# ProDocument___2023-07-26.net
KiCad netlist of a schematic drawn in EasyEDA Pro
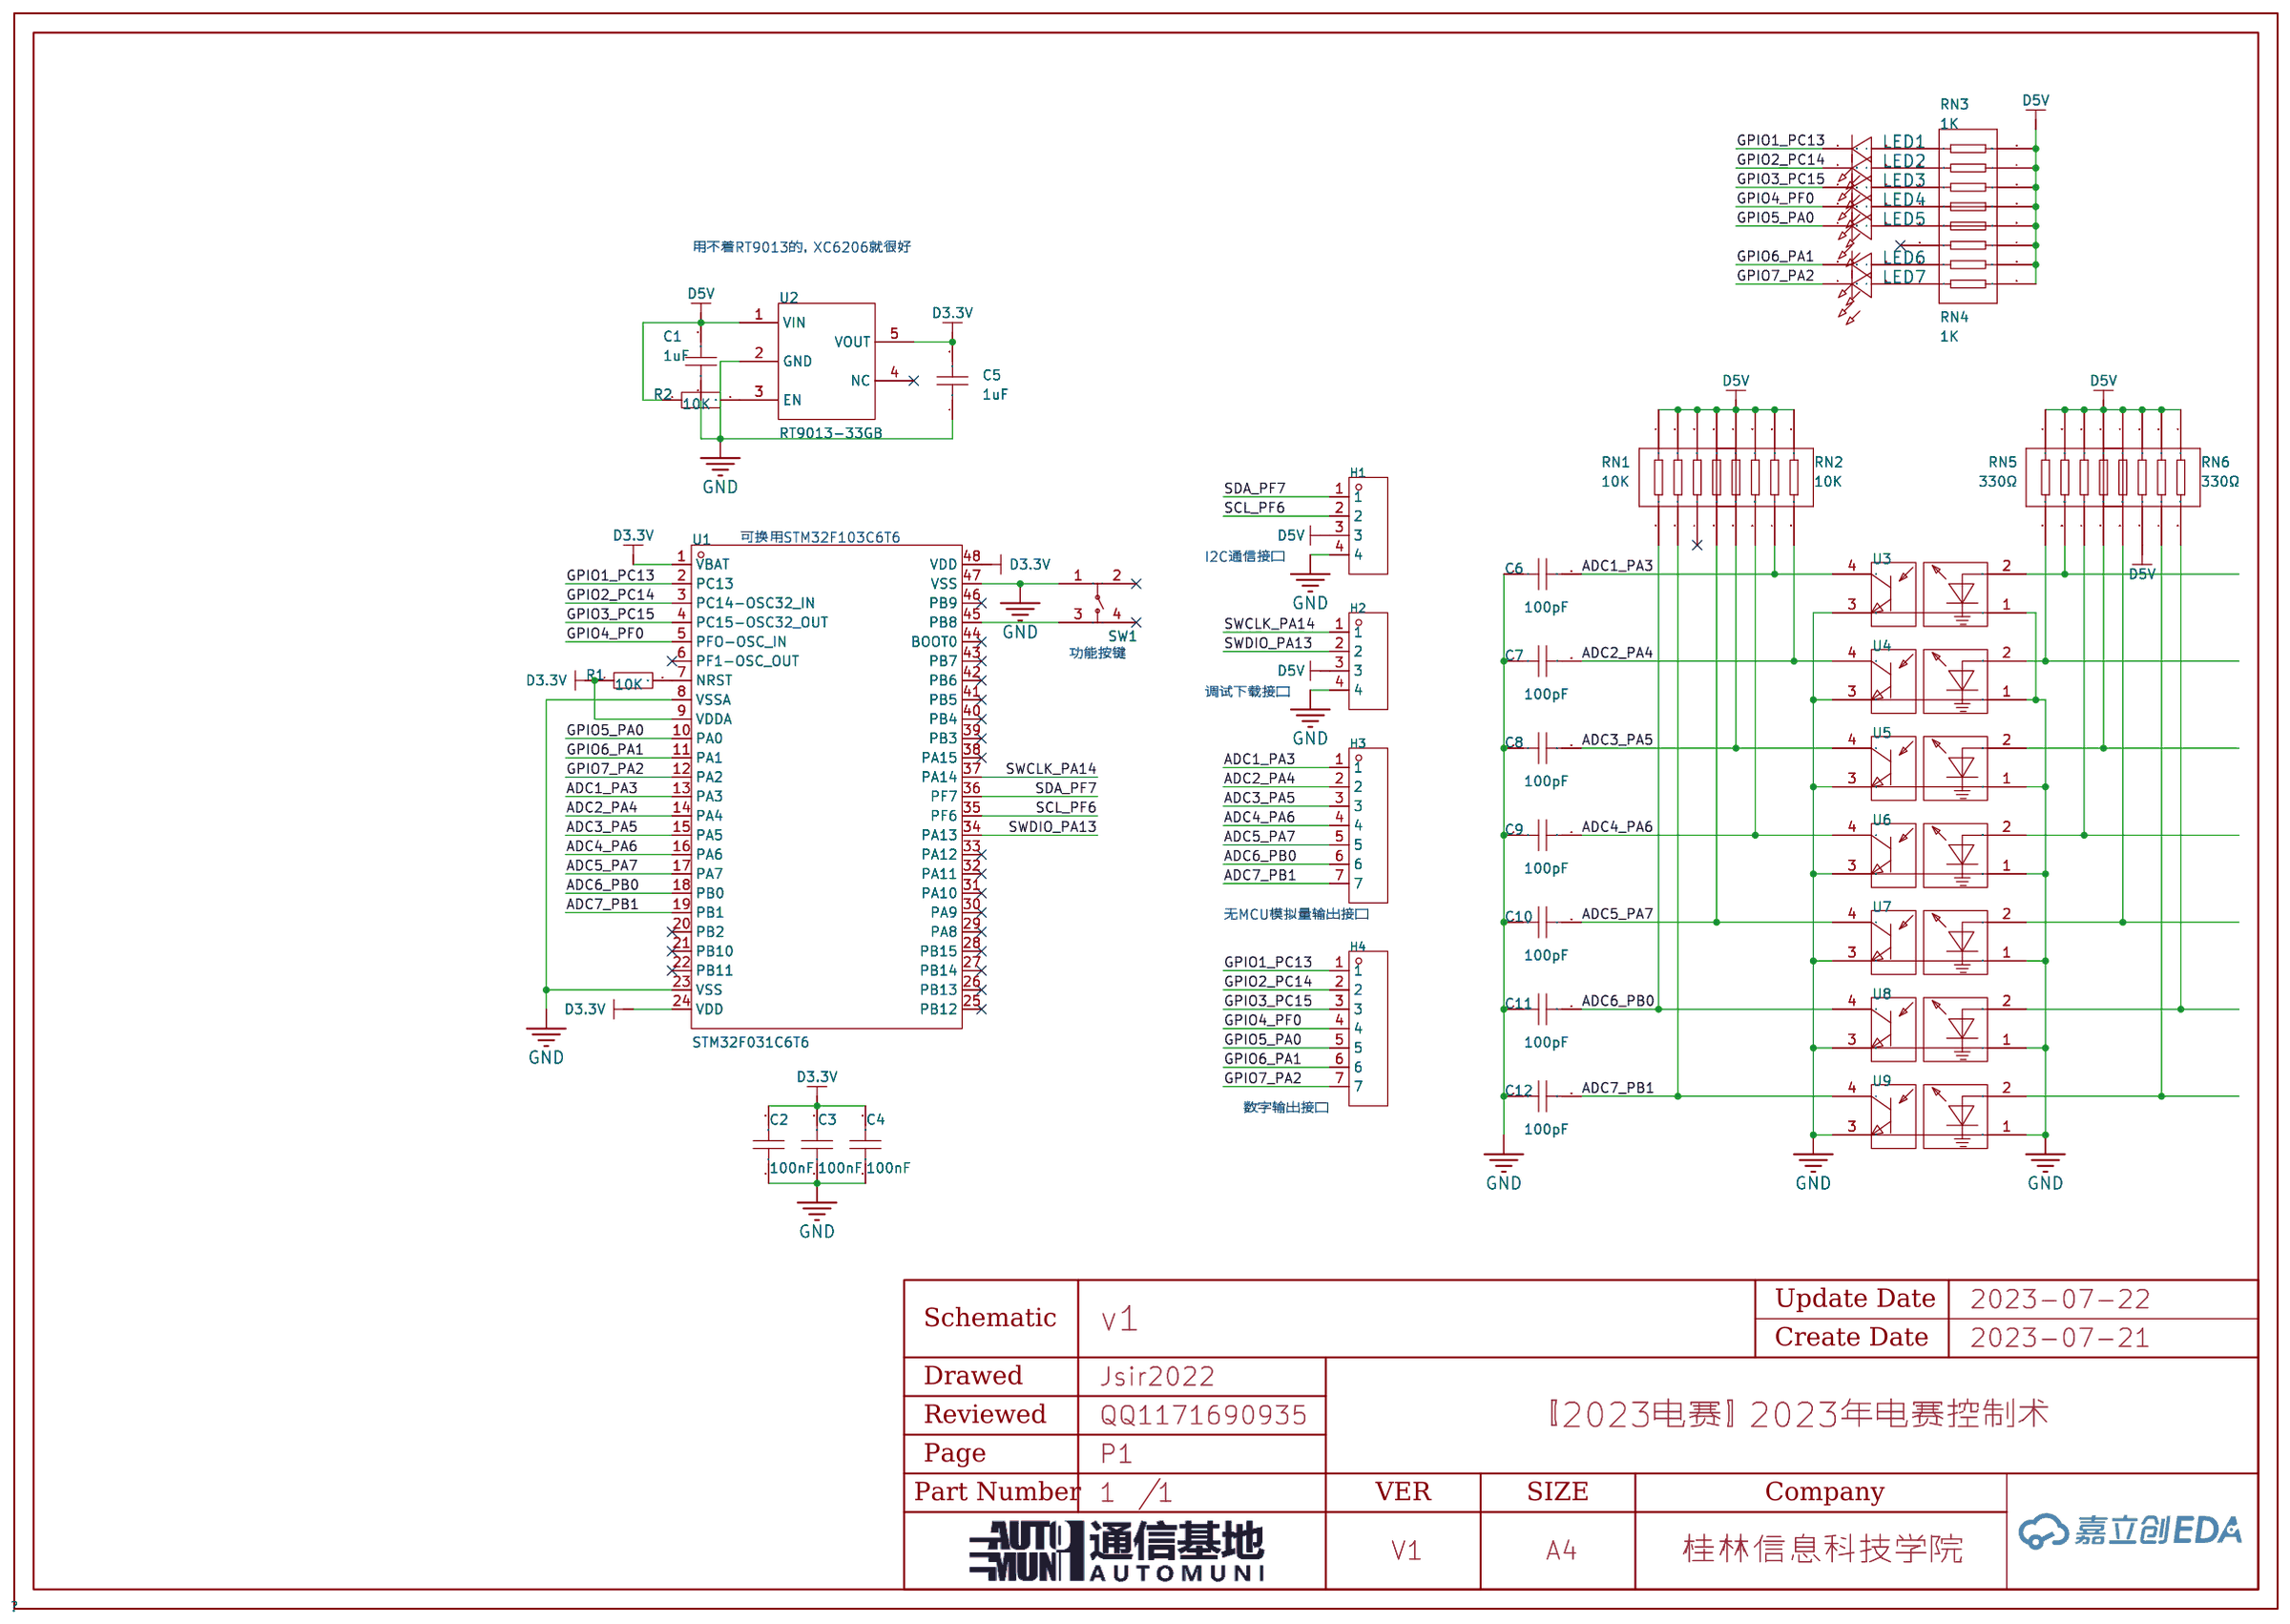
[diagram p0: schematic sheet]

(export (version "E")
  (design (tool "Eeschema 10.0.6"))
  (components
    (comp (ref "C1")
      (value "1uF")
      (footprint "easyedapro:C0603")
      (libsource (lib "easyedapro") (part "CapAcitance"))
    )
    (comp (ref "C2")
      (value "100nF")
      (footprint "easyedapro:C0603")
      (libsource (lib "easyedapro") (part "CapAcitance"))
    )
    (comp (ref "C3")
      (value "100nF")
      (footprint "easyedapro:C0603")
      (libsource (lib "easyedapro") (part "CapAcitance"))
    )
    (comp (ref "C4")
      (value "100nF")
      (footprint "easyedapro:C0603")
      (libsource (lib "easyedapro") (part "CapAcitance"))
    )
    (comp (ref "C5")
      (value "1uF")
      (footprint "easyedapro:C0603")
      (libsource (lib "easyedapro") (part "CapAcitance"))
    )
    (comp (ref "C6")
      (value "100pF")
      (footprint "easyedapro:C0603")
      (libsource (lib "easyedapro") (part "CapAcitance"))
    )
    (comp (ref "C7")
      (value "100pF")
      (footprint "easyedapro:C0603")
      (libsource (lib "easyedapro") (part "CapAcitance"))
    )
    (comp (ref "C8")
      (value "100pF")
      (footprint "easyedapro:C0603")
      (libsource (lib "easyedapro") (part "CapAcitance"))
    )
    (comp (ref "C9")
      (value "100pF")
      (footprint "easyedapro:C0603")
      (libsource (lib "easyedapro") (part "CapAcitance"))
    )
    (comp (ref "C10")
      (value "100pF")
      (footprint "easyedapro:C0603")
      (libsource (lib "easyedapro") (part "CapAcitance"))
    )
    (comp (ref "C11")
      (value "100pF")
      (footprint "easyedapro:C0603")
      (libsource (lib "easyedapro") (part "CapAcitance"))
    )
    (comp (ref "C12")
      (value "100pF")
      (footprint "easyedapro:C0603")
      (libsource (lib "easyedapro") (part "CapAcitance"))
    )
    (comp (ref "H1")
      (value "~")
      (footprint "easyedapro:HDR-TH_4P-P2.54-V-M")
      (libsource (lib "easyedapro") (part "PZ254V-11-04P"))
    )
    (comp (ref "H2")
      (value "~")
      (footprint "easyedapro:HDR-TH_4P-P2.54-V-M")
      (libsource (lib "easyedapro") (part "PZ254V-11-04P"))
    )
    (comp (ref "H3")
      (value "~")
      (footprint "easyedapro:HDR-TH_7P-P2.54-V-M")
      (libsource (lib "easyedapro") (part "PZ254V-11-07P"))
    )
    (comp (ref "H4")
      (value "~")
      (footprint "easyedapro:HDR-TH_7P-P2.54-V-M")
      (libsource (lib "easyedapro") (part "PZ254V-11-07P"))
    )
    (comp (ref "LED1")
      (value "~")
      (footprint "easyedapro:LED_0603")
      (libsource (lib "easyedapro") (part "LED_R"))
    )
    (comp (ref "LED2")
      (value "~")
      (footprint "easyedapro:LED_0603")
      (libsource (lib "easyedapro") (part "LED_R"))
    )
    (comp (ref "LED3")
      (value "~")
      (footprint "easyedapro:LED_0603")
      (libsource (lib "easyedapro") (part "LED_R"))
    )
    (comp (ref "LED4")
      (value "~")
      (footprint "easyedapro:LED_0603")
      (libsource (lib "easyedapro") (part "LED_R"))
    )
    (comp (ref "LED5")
      (value "~")
      (footprint "easyedapro:LED_0603")
      (libsource (lib "easyedapro") (part "LED_R"))
    )
    (comp (ref "LED6")
      (value "~")
      (footprint "easyedapro:LED_0603")
      (libsource (lib "easyedapro") (part "LED_R"))
    )
    (comp (ref "LED7")
      (value "~")
      (footprint "easyedapro:LED_0603")
      (libsource (lib "easyedapro") (part "LED_R"))
    )
    (comp (ref "R1") (value "10K") (footprint "easyedapro:R0603") (libsource (lib "easyedapro") (part "电阻")))
    (comp (ref "R2") (value "10K") (footprint "easyedapro:R0603") (libsource (lib "easyedapro") (part "电阻")))
    (comp (ref "RN1")
      (value "10K")
      (footprint "easyedapro:RES-ARRAY-SMD_0402-8P-L2.0-W1.0-BL")
      (description "阻值:330Ω;精度:±5%;单个元件功率:62.5mW;电阻器数:4;")
      (fields (field (name "Manufacturer Part") "YC124-JR-07330RL") (field (name "Manufacturer") "YAGEO(国巨)"))
      (libsource (lib "easyedapro") (part "YC124-JR-07330RL"))
    )
    (comp (ref "RN2")
      (value "10K")
      (footprint "easyedapro:RES-ARRAY-SMD_0402-8P-L2.0-W1.0-BL")
      (description "阻值:330Ω;精度:±5%;单个元件功率:62.5mW;电阻器数:4;")
      (fields (field (name "Manufacturer Part") "YC124-JR-07330RL") (field (name "Manufacturer") "YAGEO(国巨)"))
      (libsource (lib "easyedapro") (part "YC124-JR-07330RL"))
    )
    (comp (ref "RN3")
      (value "1K")
      (footprint "easyedapro:RES-ARRAY-SMD_0402-8P-L2.0-W1.0-BL")
      (description "阻值:330Ω;精度:±5%;单个元件功率:62.5mW;电阻器数:4;")
      (fields (field (name "Manufacturer Part") "YC124-JR-07330RL") (field (name "Manufacturer") "YAGEO(国巨)"))
      (libsource (lib "easyedapro") (part "YC124-JR-07330RL"))
    )
    (comp (ref "RN4")
      (value "1K")
      (footprint "easyedapro:RES-ARRAY-SMD_0402-8P-L2.0-W1.0-BL")
      (description "阻值:330Ω;精度:±5%;单个元件功率:62.5mW;电阻器数:4;")
      (fields (field (name "Manufacturer Part") "YC124-JR-07330RL") (field (name "Manufacturer") "YAGEO(国巨)"))
      (libsource (lib "easyedapro") (part "YC124-JR-07330RL"))
    )
    (comp (ref "RN5")
      (value "330Ω")
      (footprint "easyedapro:RES-ARRAY-SMD_0402-8P-L2.0-W1.0-BL")
      (description "阻值:330Ω;精度:±5%;单个元件功率:62.5mW;电阻器数:4;")
      (fields (field (name "Manufacturer Part") "YC124-JR-07330RL") (field (name "Manufacturer") "YAGEO(国巨)"))
      (libsource (lib "easyedapro") (part "YC124-JR-07330RL"))
    )
    (comp (ref "RN6")
      (value "330Ω")
      (footprint "easyedapro:RES-ARRAY-SMD_0402-8P-L2.0-W1.0-BL")
      (description "阻值:330Ω;精度:±5%;单个元件功率:62.5mW;电阻器数:4;")
      (fields (field (name "Manufacturer Part") "YC124-JR-07330RL") (field (name "Manufacturer") "YAGEO(国巨)"))
      (libsource (lib "easyedapro") (part "YC124-JR-07330RL"))
    )
    (comp (ref "SW1")
      (value "TS-1089S-AR02516")
      (footprint "easyedapro:SW-SMD_4P-L4.2-W3.3-P2.15-LS5.1")
      (fields (field (name "Manufacturer") "XUNPU(讯普)"))
      (libsource (lib "easyedapro") (part "TS-1089S-AR02516"))
    )
    (comp (ref "U1")
      (value "STM32F031C6T6")
      (footprint "easyedapro:LQFP-48_L7.0-W7.0-P0.50-LS9.0-BL")
      (fields (field (name "Manufacturer") "ST(意法半导体)"))
      (libsource (lib "easyedapro") (part "STM32F031C6T6"))
    )
    (comp (ref "U2")
      (value "RT9013-33GB")
      (footprint "easyedapro:SOT-23-5_L3.0-W1.7-P0.95-LS2.8-BL")
      (description "输出类型:固定;输出极性:正;最大输入电压:5.5V;输出电压:3.3V;输出电流:500mA;电源纹波抑制比(PSRR):50dB@(10kHz);")
      (fields (field (name "Manufacturer") "RICHTEK(立锜)"))
      (libsource (lib "easyedapro") (part "RT9013-33GB"))
    )
    (comp (ref "U3")
      (value "ITR9909")
      (footprint "easyedapro:OPTO-TH_ITR9909")
      (fields (field (name "Manufacturer") "EVERLIGHT(台湾亿光)"))
      (libsource (lib "easyedapro") (part "ITR9909"))
    )
    (comp (ref "U4")
      (value "ITR9909")
      (footprint "easyedapro:OPTO-TH_ITR9909")
      (fields (field (name "Manufacturer") "EVERLIGHT(台湾亿光)"))
      (libsource (lib "easyedapro") (part "ITR9909"))
    )
    (comp (ref "U5")
      (value "ITR9909")
      (footprint "easyedapro:OPTO-TH_ITR9909")
      (fields (field (name "Manufacturer") "EVERLIGHT(台湾亿光)"))
      (libsource (lib "easyedapro") (part "ITR9909"))
    )
    (comp (ref "U6")
      (value "ITR9909")
      (footprint "easyedapro:OPTO-TH_ITR9909")
      (fields (field (name "Manufacturer") "EVERLIGHT(台湾亿光)"))
      (libsource (lib "easyedapro") (part "ITR9909"))
    )
    (comp (ref "U7")
      (value "ITR9909")
      (footprint "easyedapro:OPTO-TH_ITR9909")
      (fields (field (name "Manufacturer") "EVERLIGHT(台湾亿光)"))
      (libsource (lib "easyedapro") (part "ITR9909"))
    )
    (comp (ref "U8")
      (value "ITR9909")
      (footprint "easyedapro:OPTO-TH_ITR9909")
      (fields (field (name "Manufacturer") "EVERLIGHT(台湾亿光)"))
      (libsource (lib "easyedapro") (part "ITR9909"))
    )
    (comp (ref "U9")
      (value "ITR9909")
      (footprint "easyedapro:OPTO-TH_ITR9909")
      (fields (field (name "Manufacturer") "EVERLIGHT(台湾亿光)"))
      (libsource (lib "easyedapro") (part "ITR9909"))
    )
  )
  (nets
    (net (code "1") (name "/ADC1_PA3") (class "Default")
      (node (ref "C6") (pin "2") (pinfunction "2_2") (pintype "input"))
      (node (ref "H3") (pin "1") (pinfunction "1_1") (pintype "input"))
      (node (ref "RN2") (pin "7") (pinfunction "7_7") (pintype "input"))
      (node (ref "U1") (pin "13") (pinfunction "PA3_13") (pintype "input"))
      (node (ref "U3") (pin "4") (pinfunction "4_4") (pintype "input"))
    )
    (net (code "2") (name "/ADC2_PA4") (class "Default")
      (node (ref "C7") (pin "2") (pinfunction "2_2") (pintype "input"))
      (node (ref "H3") (pin "2") (pinfunction "2_2") (pintype "input"))
      (node (ref "RN2") (pin "8") (pinfunction "8_8") (pintype "input"))
      (node (ref "U1") (pin "14") (pinfunction "PA4_14") (pintype "input"))
      (node (ref "U4") (pin "4") (pinfunction "4_4") (pintype "input"))
    )
    (net (code "3") (name "/ADC3_PA5") (class "Default")
      (node (ref "C8") (pin "2") (pinfunction "2_2") (pintype "input"))
      (node (ref "H3") (pin "3") (pinfunction "3_3") (pintype "input"))
      (node (ref "RN2") (pin "5") (pinfunction "5_5") (pintype "input"))
      (node (ref "U1") (pin "15") (pinfunction "PA5_15") (pintype "input"))
      (node (ref "U5") (pin "4") (pinfunction "4_4") (pintype "input"))
    )
    (net (code "4") (name "/ADC4_PA6") (class "Default")
      (node (ref "C9") (pin "2") (pinfunction "2_2") (pintype "input"))
      (node (ref "H3") (pin "4") (pinfunction "4_4") (pintype "input"))
      (node (ref "RN2") (pin "6") (pinfunction "6_6") (pintype "input"))
      (node (ref "U1") (pin "16") (pinfunction "PA6_16") (pintype "input"))
      (node (ref "U6") (pin "4") (pinfunction "4_4") (pintype "input"))
    )
    (net (code "5") (name "/ADC5_PA7") (class "Default")
      (node (ref "C10") (pin "2") (pinfunction "2_2") (pintype "input"))
      (node (ref "H3") (pin "5") (pinfunction "5_5") (pintype "input"))
      (node (ref "RN1") (pin "8") (pinfunction "8_8") (pintype "input"))
      (node (ref "U1") (pin "17") (pinfunction "PA7_17") (pintype "input"))
      (node (ref "U7") (pin "4") (pinfunction "4_4") (pintype "input"))
    )
    (net (code "6") (name "/ADC6_PB0") (class "Default")
      (node (ref "C11") (pin "2") (pinfunction "2_2") (pintype "input"))
      (node (ref "H3") (pin "6") (pinfunction "6_6") (pintype "input"))
      (node (ref "RN1") (pin "5") (pinfunction "5_5") (pintype "input"))
      (node (ref "U1") (pin "18") (pinfunction "PB0_18") (pintype "input"))
      (node (ref "U8") (pin "4") (pinfunction "4_4") (pintype "input"))
    )
    (net (code "7") (name "/ADC7_PB1") (class "Default")
      (node (ref "C12") (pin "2") (pinfunction "2_2") (pintype "input"))
      (node (ref "H3") (pin "7") (pinfunction "7_7") (pintype "input"))
      (node (ref "RN1") (pin "6") (pinfunction "6_6") (pintype "input"))
      (node (ref "U1") (pin "19") (pinfunction "PB1_19") (pintype "input"))
      (node (ref "U9") (pin "4") (pinfunction "4_4") (pintype "input"))
    )
    (net (code "8") (name "/GPIO1_PC13") (class "Default")
      (node (ref "H4") (pin "1") (pinfunction "1_1") (pintype "input"))
      (node (ref "LED1") (pin "1") (pinfunction "C_1") (pintype "input"))
      (node (ref "U1") (pin "2") (pinfunction "PC13_2") (pintype "input"))
    )
    (net (code "9") (name "/GPIO2_PC14") (class "Default")
      (node (ref "H4") (pin "2") (pinfunction "2_2") (pintype "input"))
      (node (ref "LED2") (pin "1") (pinfunction "C_1") (pintype "input"))
      (node (ref "U1") (pin "3") (pinfunction "PC14-OSC32_IN_3") (pintype "input"))
    )
    (net (code "10") (name "/GPIO3_PC15") (class "Default")
      (node (ref "H4") (pin "3") (pinfunction "3_3") (pintype "input"))
      (node (ref "LED3") (pin "1") (pinfunction "C_1") (pintype "input"))
      (node (ref "U1") (pin "4") (pinfunction "PC15-OSC32_OUT_4") (pintype "input"))
    )
    (net (code "11") (name "/GPIO4_PF0") (class "Default")
      (node (ref "H4") (pin "4") (pinfunction "4_4") (pintype "input"))
      (node (ref "LED4") (pin "1") (pinfunction "C_1") (pintype "input"))
      (node (ref "U1") (pin "5") (pinfunction "PFO-OSC_IN_5") (pintype "input"))
    )
    (net (code "12") (name "/GPIO5_PA0") (class "Default")
      (node (ref "H4") (pin "5") (pinfunction "5_5") (pintype "input"))
      (node (ref "LED5") (pin "1") (pinfunction "C_1") (pintype "input"))
      (node (ref "U1") (pin "10") (pinfunction "PA0_10") (pintype "input"))
    )
    (net (code "13") (name "/GPIO6_PA1") (class "Default")
      (node (ref "H4") (pin "6") (pinfunction "6_6") (pintype "input"))
      (node (ref "LED6") (pin "1") (pinfunction "C_1") (pintype "input"))
      (node (ref "U1") (pin "11") (pinfunction "PA1_11") (pintype "input"))
    )
    (net (code "14") (name "/GPIO7_PA2") (class "Default")
      (node (ref "H4") (pin "7") (pinfunction "7_7") (pintype "input"))
      (node (ref "LED7") (pin "1") (pinfunction "C_1") (pintype "input"))
      (node (ref "U1") (pin "12") (pinfunction "PA2_12") (pintype "input"))
    )
    (net (code "15") (name "/SCL_PF6") (class "Default")
      (node (ref "H1") (pin "2") (pinfunction "2_2") (pintype "input"))
      (node (ref "U1") (pin "35") (pinfunction "PF6_35") (pintype "input"))
    )
    (net (code "16") (name "/SDA_PF7") (class "Default")
      (node (ref "H1") (pin "1") (pinfunction "1_1") (pintype "input"))
      (node (ref "U1") (pin "36") (pinfunction "PF7_36") (pintype "input"))
    )
    (net (code "17") (name "/SWCLK_PA14") (class "Default")
      (node (ref "H2") (pin "1") (pinfunction "1_1") (pintype "input"))
      (node (ref "U1") (pin "37") (pinfunction "PA14_37") (pintype "input"))
    )
    (net (code "18") (name "/SWDIO_PA13") (class "Default")
      (node (ref "H2") (pin "2") (pinfunction "2_2") (pintype "input"))
      (node (ref "U1") (pin "34") (pinfunction "PA13_34") (pintype "input"))
    )
    (net (code "19") (name "D3.3V") (class "Default")
      (node (ref "C2") (pin "2") (pinfunction "2_2") (pintype "input"))
      (node (ref "C3") (pin "2") (pinfunction "2_2") (pintype "input"))
      (node (ref "C4") (pin "2") (pinfunction "2_2") (pintype "input"))
      (node (ref "C5") (pin "2") (pinfunction "2_2") (pintype "input"))
      (node (ref "R1") (pin "1") (pinfunction "1_1") (pintype "input"))
      (node (ref "U1") (pin "1") (pinfunction "VBAT_1") (pintype "input"))
      (node (ref "U1") (pin "24") (pinfunction "VDD_24") (pintype "input"))
      (node (ref "U1") (pin "48") (pinfunction "VDD_48") (pintype "input"))
      (node (ref "U1") (pin "9") (pinfunction "VDDA_9") (pintype "input"))
      (node (ref "U2") (pin "5") (pinfunction "VOUT_5") (pintype "input"))
    )
    (net (code "20") (name "D5V") (class "Default")
      (node (ref "C1") (pin "2") (pinfunction "2_2") (pintype "input"))
      (node (ref "H1") (pin "3") (pinfunction "3_3") (pintype "input"))
      (node (ref "H2") (pin "3") (pinfunction "3_3") (pintype "input"))
      (node (ref "R2") (pin "1") (pinfunction "1_1") (pintype "input"))
      (node (ref "RN1") (pin "1") (pinfunction "1_1") (pintype "input"))
      (node (ref "RN1") (pin "2") (pinfunction "2_2") (pintype "input"))
      (node (ref "RN1") (pin "3") (pinfunction "3_3") (pintype "input"))
      (node (ref "RN1") (pin "4") (pinfunction "4_4") (pintype "input"))
      (node (ref "RN2") (pin "1") (pinfunction "1_1") (pintype "input"))
      (node (ref "RN2") (pin "2") (pinfunction "2_2") (pintype "input"))
      (node (ref "RN2") (pin "3") (pinfunction "3_3") (pintype "input"))
      (node (ref "RN2") (pin "4") (pinfunction "4_4") (pintype "input"))
      (node (ref "RN3") (pin "5") (pinfunction "5_5") (pintype "input"))
      (node (ref "RN3") (pin "6") (pinfunction "6_6") (pintype "input"))
      (node (ref "RN3") (pin "7") (pinfunction "7_7") (pintype "input"))
      (node (ref "RN3") (pin "8") (pinfunction "8_8") (pintype "input"))
      (node (ref "RN4") (pin "5") (pinfunction "5_5") (pintype "input"))
      (node (ref "RN4") (pin "6") (pinfunction "6_6") (pintype "input"))
      (node (ref "RN4") (pin "7") (pinfunction "7_7") (pintype "input"))
      (node (ref "RN4") (pin "8") (pinfunction "8_8") (pintype "input"))
      (node (ref "RN5") (pin "1") (pinfunction "1_1") (pintype "input"))
      (node (ref "RN5") (pin "2") (pinfunction "2_2") (pintype "input"))
      (node (ref "RN5") (pin "3") (pinfunction "3_3") (pintype "input"))
      (node (ref "RN5") (pin "4") (pinfunction "4_4") (pintype "input"))
      (node (ref "RN6") (pin "1") (pinfunction "1_1") (pintype "input"))
      (node (ref "RN6") (pin "2") (pinfunction "2_2") (pintype "input"))
      (node (ref "RN6") (pin "3") (pinfunction "3_3") (pintype "input"))
      (node (ref "RN6") (pin "4") (pinfunction "4_4") (pintype "input"))
      (node (ref "RN6") (pin "6") (pinfunction "6_6") (pintype "input"))
      (node (ref "U2") (pin "1") (pinfunction "VIN_1") (pintype "input"))
    )
    (net (code "21") (name "GND") (class "Default")
      (node (ref "C1") (pin "1") (pinfunction "1_1") (pintype "input"))
      (node (ref "C10") (pin "1") (pinfunction "1_1") (pintype "input"))
      (node (ref "C11") (pin "1") (pinfunction "1_1") (pintype "input"))
      (node (ref "C12") (pin "1") (pinfunction "1_1") (pintype "input"))
      (node (ref "C2") (pin "1") (pinfunction "1_1") (pintype "input"))
      (node (ref "C3") (pin "1") (pinfunction "1_1") (pintype "input"))
      (node (ref "C4") (pin "1") (pinfunction "1_1") (pintype "input"))
      (node (ref "C5") (pin "1") (pinfunction "1_1") (pintype "input"))
      (node (ref "C6") (pin "1") (pinfunction "1_1") (pintype "input"))
      (node (ref "C7") (pin "1") (pinfunction "1_1") (pintype "input"))
      (node (ref "C8") (pin "1") (pinfunction "1_1") (pintype "input"))
      (node (ref "C9") (pin "1") (pinfunction "1_1") (pintype "input"))
      (node (ref "H1") (pin "4") (pinfunction "4_4") (pintype "input"))
      (node (ref "H2") (pin "4") (pinfunction "4_4") (pintype "input"))
      (node (ref "SW1") (pin "1") (pinfunction "1_1") (pintype "input"))
      (node (ref "U1") (pin "23") (pinfunction "VSS_23") (pintype "input"))
      (node (ref "U1") (pin "47") (pinfunction "VSS_47") (pintype "input"))
      (node (ref "U1") (pin "8") (pinfunction "VSSA_8") (pintype "input"))
      (node (ref "U2") (pin "2") (pinfunction "GND_2") (pintype "input"))
      (node (ref "U3") (pin "1") (pinfunction "1_1") (pintype "input"))
      (node (ref "U3") (pin "3") (pinfunction "3_3") (pintype "input"))
      (node (ref "U4") (pin "1") (pinfunction "1_1") (pintype "input"))
      (node (ref "U4") (pin "3") (pinfunction "3_3") (pintype "input"))
      (node (ref "U5") (pin "1") (pinfunction "1_1") (pintype "input"))
      (node (ref "U5") (pin "3") (pinfunction "3_3") (pintype "input"))
      (node (ref "U6") (pin "1") (pinfunction "1_1") (pintype "input"))
      (node (ref "U6") (pin "3") (pinfunction "3_3") (pintype "input"))
      (node (ref "U7") (pin "1") (pinfunction "1_1") (pintype "input"))
      (node (ref "U7") (pin "3") (pinfunction "3_3") (pintype "input"))
      (node (ref "U8") (pin "1") (pinfunction "1_1") (pintype "input"))
      (node (ref "U8") (pin "3") (pinfunction "3_3") (pintype "input"))
      (node (ref "U9") (pin "1") (pinfunction "1_1") (pintype "input"))
      (node (ref "U9") (pin "3") (pinfunction "3_3") (pintype "input"))
    )
    (net (code "22") (name "Net-(LED1-A)") (class "Default")
      (node (ref "LED1") (pin "2") (pinfunction "A_2") (pintype "input"))
      (node (ref "RN3") (pin "1") (pinfunction "1_1") (pintype "input"))
    )
    (net (code "23") (name "Net-(LED2-A)") (class "Default")
      (node (ref "LED2") (pin "2") (pinfunction "A_2") (pintype "input"))
      (node (ref "RN3") (pin "2") (pinfunction "2_2") (pintype "input"))
    )
    (net (code "24") (name "Net-(LED3-A)") (class "Default")
      (node (ref "LED3") (pin "2") (pinfunction "A_2") (pintype "input"))
      (node (ref "RN3") (pin "3") (pinfunction "3_3") (pintype "input"))
    )
    (net (code "25") (name "Net-(LED4-A)") (class "Default")
      (node (ref "LED4") (pin "2") (pinfunction "A_2") (pintype "input"))
      (node (ref "RN3") (pin "4") (pinfunction "4_4") (pintype "input"))
    )
    (net (code "26") (name "Net-(LED5-A)") (class "Default")
      (node (ref "LED5") (pin "2") (pinfunction "A_2") (pintype "input"))
      (node (ref "RN4") (pin "1") (pinfunction "1_1") (pintype "input"))
    )
    (net (code "27") (name "Net-(LED6-A)") (class "Default")
      (node (ref "LED6") (pin "2") (pinfunction "A_2") (pintype "input"))
      (node (ref "RN4") (pin "3") (pinfunction "3_3") (pintype "input"))
    )
    (net (code "28") (name "Net-(LED7-A)") (class "Default")
      (node (ref "LED7") (pin "2") (pinfunction "A_2") (pintype "input"))
      (node (ref "RN4") (pin "4") (pinfunction "4_4") (pintype "input"))
    )
    (net (code "29") (name "Net-(RN5-Pad5)") (class "Default")
      (node (ref "RN5") (pin "5") (pinfunction "5_5") (pintype "input"))
      (node (ref "U4") (pin "2") (pinfunction "2_2") (pintype "input"))
    )
    (net (code "30") (name "Net-(RN5-Pad6)") (class "Default")
      (node (ref "RN5") (pin "6") (pinfunction "6_6") (pintype "input"))
      (node (ref "U3") (pin "2") (pinfunction "2_2") (pintype "input"))
    )
    (net (code "31") (name "Net-(RN5-Pad7)") (class "Default")
      (node (ref "RN5") (pin "7") (pinfunction "7_7") (pintype "input"))
      (node (ref "U6") (pin "2") (pinfunction "2_2") (pintype "input"))
    )
    (net (code "32") (name "Net-(RN5-Pad8)") (class "Default")
      (node (ref "RN5") (pin "8") (pinfunction "8_8") (pintype "input"))
      (node (ref "U5") (pin "2") (pinfunction "2_2") (pintype "input"))
    )
    (net (code "33") (name "Net-(RN6-Pad5)") (class "Default")
      (node (ref "RN6") (pin "5") (pinfunction "5_5") (pintype "input"))
      (node (ref "U7") (pin "2") (pinfunction "2_2") (pintype "input"))
    )
    (net (code "34") (name "Net-(RN6-Pad7)") (class "Default")
      (node (ref "RN6") (pin "7") (pinfunction "7_7") (pintype "input"))
      (node (ref "U9") (pin "2") (pinfunction "2_2") (pintype "input"))
    )
    (net (code "35") (name "Net-(RN6-Pad8)") (class "Default")
      (node (ref "RN6") (pin "8") (pinfunction "8_8") (pintype "input"))
      (node (ref "U8") (pin "2") (pinfunction "2_2") (pintype "input"))
    )
    (net (code "36") (name "Net-(U1-NRST)") (class "Default")
      (node (ref "R1") (pin "2") (pinfunction "2_2") (pintype "input"))
      (node (ref "U1") (pin "7") (pinfunction "NRST_7") (pintype "input"))
    )
    (net (code "37") (name "Net-(U1-PB8)") (class "Default")
      (node (ref "SW1") (pin "3") (pinfunction "3_3") (pintype "input"))
      (node (ref "U1") (pin "45") (pinfunction "PB8_45") (pintype "input"))
    )
    (net (code "38") (name "Net-(U2-EN)") (class "Default")
      (node (ref "R2") (pin "2") (pinfunction "2_2") (pintype "input"))
      (node (ref "U2") (pin "3") (pinfunction "EN_3") (pintype "input"))
    )
    (net (code "39") (name "unconnected-(RN1-Pad7)") (class "Default")
      (node (ref "RN1") (pin "7") (pinfunction "7_7") (pintype "input+no_connect"))
    )
    (net (code "40") (name "unconnected-(RN4-Pad2)") (class "Default")
      (node (ref "RN4") (pin "2") (pinfunction "2_2") (pintype "input+no_connect"))
    )
    (net (code "41") (name "unconnected-(SW1-Pad2)") (class "Default")
      (node (ref "SW1") (pin "2") (pinfunction "2_2") (pintype "input+no_connect"))
    )
    (net (code "42") (name "unconnected-(SW1-Pad4)") (class "Default")
      (node (ref "SW1") (pin "4") (pinfunction "4_4") (pintype "input+no_connect"))
    )
    (net (code "43") (name "unconnected-(U1-BOOT0-Pad44)") (class "Default")
      (node (ref "U1") (pin "44") (pinfunction "BOOT0_44") (pintype "input+no_connect"))
    )
    (net (code "44") (name "unconnected-(U1-PA8-Pad29)") (class "Default")
      (node (ref "U1") (pin "29") (pinfunction "PA8_29") (pintype "input+no_connect"))
    )
    (net (code "45") (name "unconnected-(U1-PA9-Pad30)") (class "Default")
      (node (ref "U1") (pin "30") (pinfunction "PA9_30") (pintype "input+no_connect"))
    )
    (net (code "46") (name "unconnected-(U1-PA10-Pad31)") (class "Default")
      (node (ref "U1") (pin "31") (pinfunction "PA10_31") (pintype "input+no_connect"))
    )
    (net (code "47") (name "unconnected-(U1-PA11-Pad32)") (class "Default")
      (node (ref "U1") (pin "32") (pinfunction "PA11_32") (pintype "input+no_connect"))
    )
    (net (code "48") (name "unconnected-(U1-PA12-Pad33)") (class "Default")
      (node (ref "U1") (pin "33") (pinfunction "PA12_33") (pintype "input+no_connect"))
    )
    (net (code "49") (name "unconnected-(U1-PA15-Pad38)") (class "Default")
      (node (ref "U1") (pin "38") (pinfunction "PA15_38") (pintype "input+no_connect"))
    )
    (net (code "50") (name "unconnected-(U1-PB2-Pad20)") (class "Default")
      (node (ref "U1") (pin "20") (pinfunction "PB2_20") (pintype "input+no_connect"))
    )
    (net (code "51") (name "unconnected-(U1-PB3-Pad39)") (class "Default")
      (node (ref "U1") (pin "39") (pinfunction "PB3_39") (pintype "input+no_connect"))
    )
    (net (code "52") (name "unconnected-(U1-PB4-Pad40)") (class "Default")
      (node (ref "U1") (pin "40") (pinfunction "PB4_40") (pintype "input+no_connect"))
    )
    (net (code "53") (name "unconnected-(U1-PB5-Pad41)") (class "Default")
      (node (ref "U1") (pin "41") (pinfunction "PB5_41") (pintype "input+no_connect"))
    )
    (net (code "54") (name "unconnected-(U1-PB6-Pad42)") (class "Default")
      (node (ref "U1") (pin "42") (pinfunction "PB6_42") (pintype "input+no_connect"))
    )
    (net (code "55") (name "unconnected-(U1-PB7-Pad43)") (class "Default")
      (node (ref "U1") (pin "43") (pinfunction "PB7_43") (pintype "input+no_connect"))
    )
    (net (code "56") (name "unconnected-(U1-PB9-Pad46)") (class "Default")
      (node (ref "U1") (pin "46") (pinfunction "PB9_46") (pintype "input+no_connect"))
    )
    (net (code "57") (name "unconnected-(U1-PB10-Pad21)") (class "Default")
      (node (ref "U1") (pin "21") (pinfunction "PB10_21") (pintype "input+no_connect"))
    )
    (net (code "58") (name "unconnected-(U1-PB11-Pad22)") (class "Default")
      (node (ref "U1") (pin "22") (pinfunction "PB11_22") (pintype "input+no_connect"))
    )
    (net (code "59") (name "unconnected-(U1-PB12-Pad25)") (class "Default")
      (node (ref "U1") (pin "25") (pinfunction "PB12_25") (pintype "input+no_connect"))
    )
    (net (code "60") (name "unconnected-(U1-PB13-Pad26)") (class "Default")
      (node (ref "U1") (pin "26") (pinfunction "PB13_26") (pintype "input+no_connect"))
    )
    (net (code "61") (name "unconnected-(U1-PB14-Pad27)") (class "Default")
      (node (ref "U1") (pin "27") (pinfunction "PB14_27") (pintype "input+no_connect"))
    )
    (net (code "62") (name "unconnected-(U1-PB15-Pad28)") (class "Default")
      (node (ref "U1") (pin "28") (pinfunction "PB15_28") (pintype "input+no_connect"))
    )
    (net (code "63") (name "unconnected-(U1-PF1-OSC_OUT-Pad6)") (class "Default")
      (node (ref "U1") (pin "6") (pinfunction "PF1-OSC_OUT_6") (pintype "input+no_connect"))
    )
    (net (code "64") (name "unconnected-(U2-NC-Pad4)") (class "Default")
      (node (ref "U2") (pin "4") (pinfunction "NC_4") (pintype "input+no_connect"))
    )
  )
)
